# UBC-Thunderbots_PCB_Power__power-v3_1_pc.net
KiCad netlist of a schematic drawn in Altium Designer
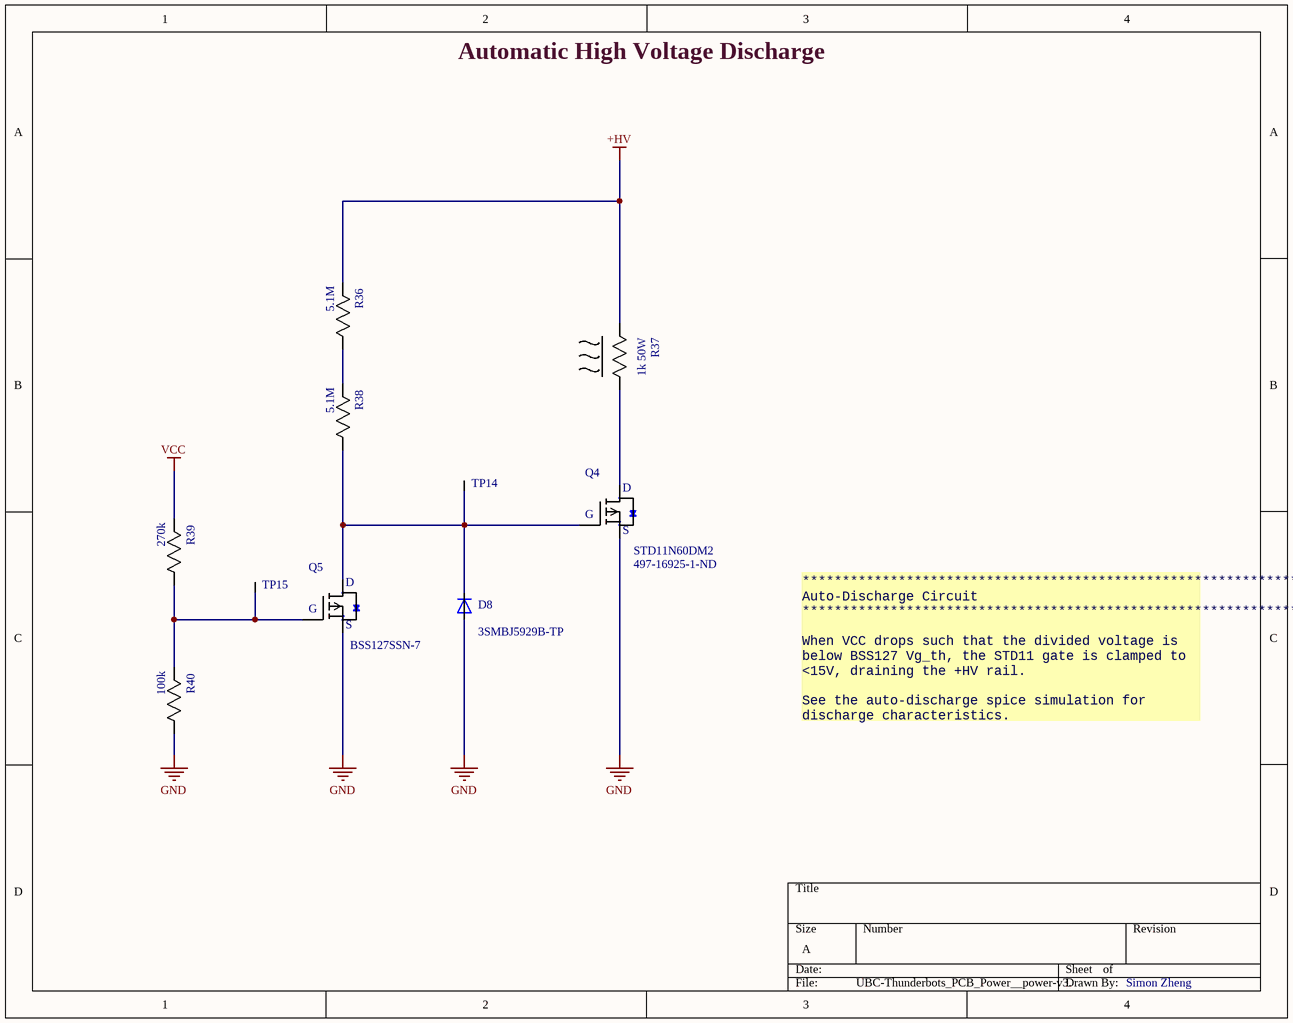
[diagram p0: UBC-Thunderbots_PCB_Power__power-v3.1_pcb__auto-discharge.SchDoc]

(export (version "E")
  (design (tool "Eeschema 10.0.6"))
  (components
    (comp (ref "D8")
      (value "3SMBJ5929B-TP")
      (footprint "DO-214AA")
      (description "Diode ZENER 15V 3W")
      (libsource (lib "AltiumLibraries") (part "DIODE ZENER 15V 3W"))
    )
    (comp (ref "Q4")
      (value "STD11N60DM2")
      (footprint "DPAK (TO-252)")
      (fields
        (field (name "MFG") "STMicroelectronics")
        (field (name "SUPPLIER PART NUMBER 1") "497-16925-1-ND")
      )
      (libsource (lib "AltiumLibraries") (part "STD11N60DM2"))
    )
    (comp (ref "Q5")
      (value "BSS127SSN-7")
      (footprint "SOT95P245X89-3M")
      (description "Small Signal N-Ch, 600Vds")
      (fields (field (name "MFG") "Diodes Incorporated"))
      (libsource (lib "AltiumLibraries") (part "BSS127SSN-7"))
    )
    (comp (ref "R36")
      (value "5.1M")
      (footprint "0603")
      (description "RES SMD 5.1 MOHM 5% 1/8W 0805")
      (fields (field (name "TOLERANCE") "5%"))
      (libsource (lib "AltiumLibraries") (part "RES 5.1M 1/8W-5%"))
    )
    (comp (ref "R37")
      (value "1k 50W")
      (footprint "D2PAK (TO-263)")
      (description "RES SMD 1.5K OHM 1% 50W D2PAK")
      (fields (field (name "TOLERANCE") "1%"))
      (libsource (lib "AltiumLibraries") (part "RES 1.5k 50W"))
    )
    (comp (ref "R38")
      (value "5.1M")
      (footprint "0603")
      (description "RES SMD 5.1 MOHM 5% 1/8W 0805")
      (fields (field (name "TOLERANCE") "5%"))
      (libsource (lib "") (part "RES 5.1M 1/8W-5%_1"))
    )
    (comp (ref "R39")
      (value "270k")
      (footprint "0805")
      (description "RES SMD 270K OHM 5% 1/8W 0805")
      (fields (field (name "TOLERANCE") "5%"))
      (libsource (lib "AltiumLibraries") (part "RES 270k 1/8W"))
    )
    (comp (ref "R40")
      (value "100k")
      (footprint "0805")
      (description "RES SMD 100K OHM 1% 1/8W 0805")
      (fields (field (name "TOLERANCE") "1%"))
      (libsource (lib "AltiumLibraries") (part "RES 100k 1/8W - 1%"))
    )
    (comp (ref "TP14")
      (value "Test Point (Via)")
      (footprint "TP")
      (libsource (lib "AltiumLibraries") (part "Test Point (Via)"))
    )
    (comp (ref "TP15")
      (value "Test Point (Via)")
      (footprint "TP")
      (libsource (lib "AltiumLibraries") (part "Test Point (Via)"))
    )
  )
  (nets
    (net (code "1") (name "+HV") (class "Default")
      (node (ref "R36") (pin "2") (pinfunction "R2_2") (pintype "passive"))
      (node (ref "R37") (pin "2") (pinfunction "R2_2") (pintype "passive"))
    )
    (net (code "2") (name "GND") (class "Default")
      (node (ref "D8") (pin "A") (pinfunction "A_A") (pintype "passive"))
      (node (ref "Q4") (pin "S") (pinfunction "S_S") (pintype "passive"))
      (node (ref "Q5") (pin "S") (pinfunction "S_S") (pintype "passive"))
      (node (ref "R40") (pin "1") (pinfunction "R1_1") (pintype "passive"))
    )
    (net (code "3") (name "Net-(R36-R1)") (class "Default")
      (node (ref "R36") (pin "1") (pinfunction "R1_1") (pintype "passive"))
      (node (ref "R38") (pin "2") (pinfunction "R2_2") (pintype "passive"))
    )
    (net (code "4") (name "Net-(R37-R1)") (class "Default")
      (node (ref "Q4") (pin "D") (pinfunction "D_D") (pintype "passive"))
      (node (ref "R37") (pin "1") (pinfunction "R1_1") (pintype "passive"))
    )
    (net (code "5") (name "Net-(R38-R1)") (class "Default")
      (node (ref "D8") (pin "C") (pinfunction "C_C") (pintype "passive"))
      (node (ref "Q4") (pin "G") (pinfunction "G_G") (pintype "passive"))
      (node (ref "Q5") (pin "D") (pinfunction "D_D") (pintype "passive"))
      (node (ref "R38") (pin "1") (pinfunction "R1_1") (pintype "passive"))
      (node (ref "TP14") (pin "1") (pinfunction "1_1") (pintype "passive"))
    )
    (net (code "6") (name "Net-(R39-R1)") (class "Default")
      (node (ref "Q5") (pin "G") (pinfunction "G_G") (pintype "passive"))
      (node (ref "R39") (pin "1") (pinfunction "R1_1") (pintype "passive"))
      (node (ref "R40") (pin "2") (pinfunction "R2_2") (pintype "passive"))
      (node (ref "TP15") (pin "1") (pinfunction "1_1") (pintype "passive"))
    )
    (net (code "7") (name "VCC") (class "Default")
      (node (ref "R39") (pin "2") (pinfunction "R2_2") (pintype "passive"))
    )
    (net (code "8") (name "unconnected-(R37-Pad3)") (class "Default")
      (node (ref "R37") (pin "3") (pinfunction "3_3") (pintype "passive"))
    )
  )
)
